# llrf_fmc_ext_female.net
KiCad netlist of a schematic drawn in Altium Designer
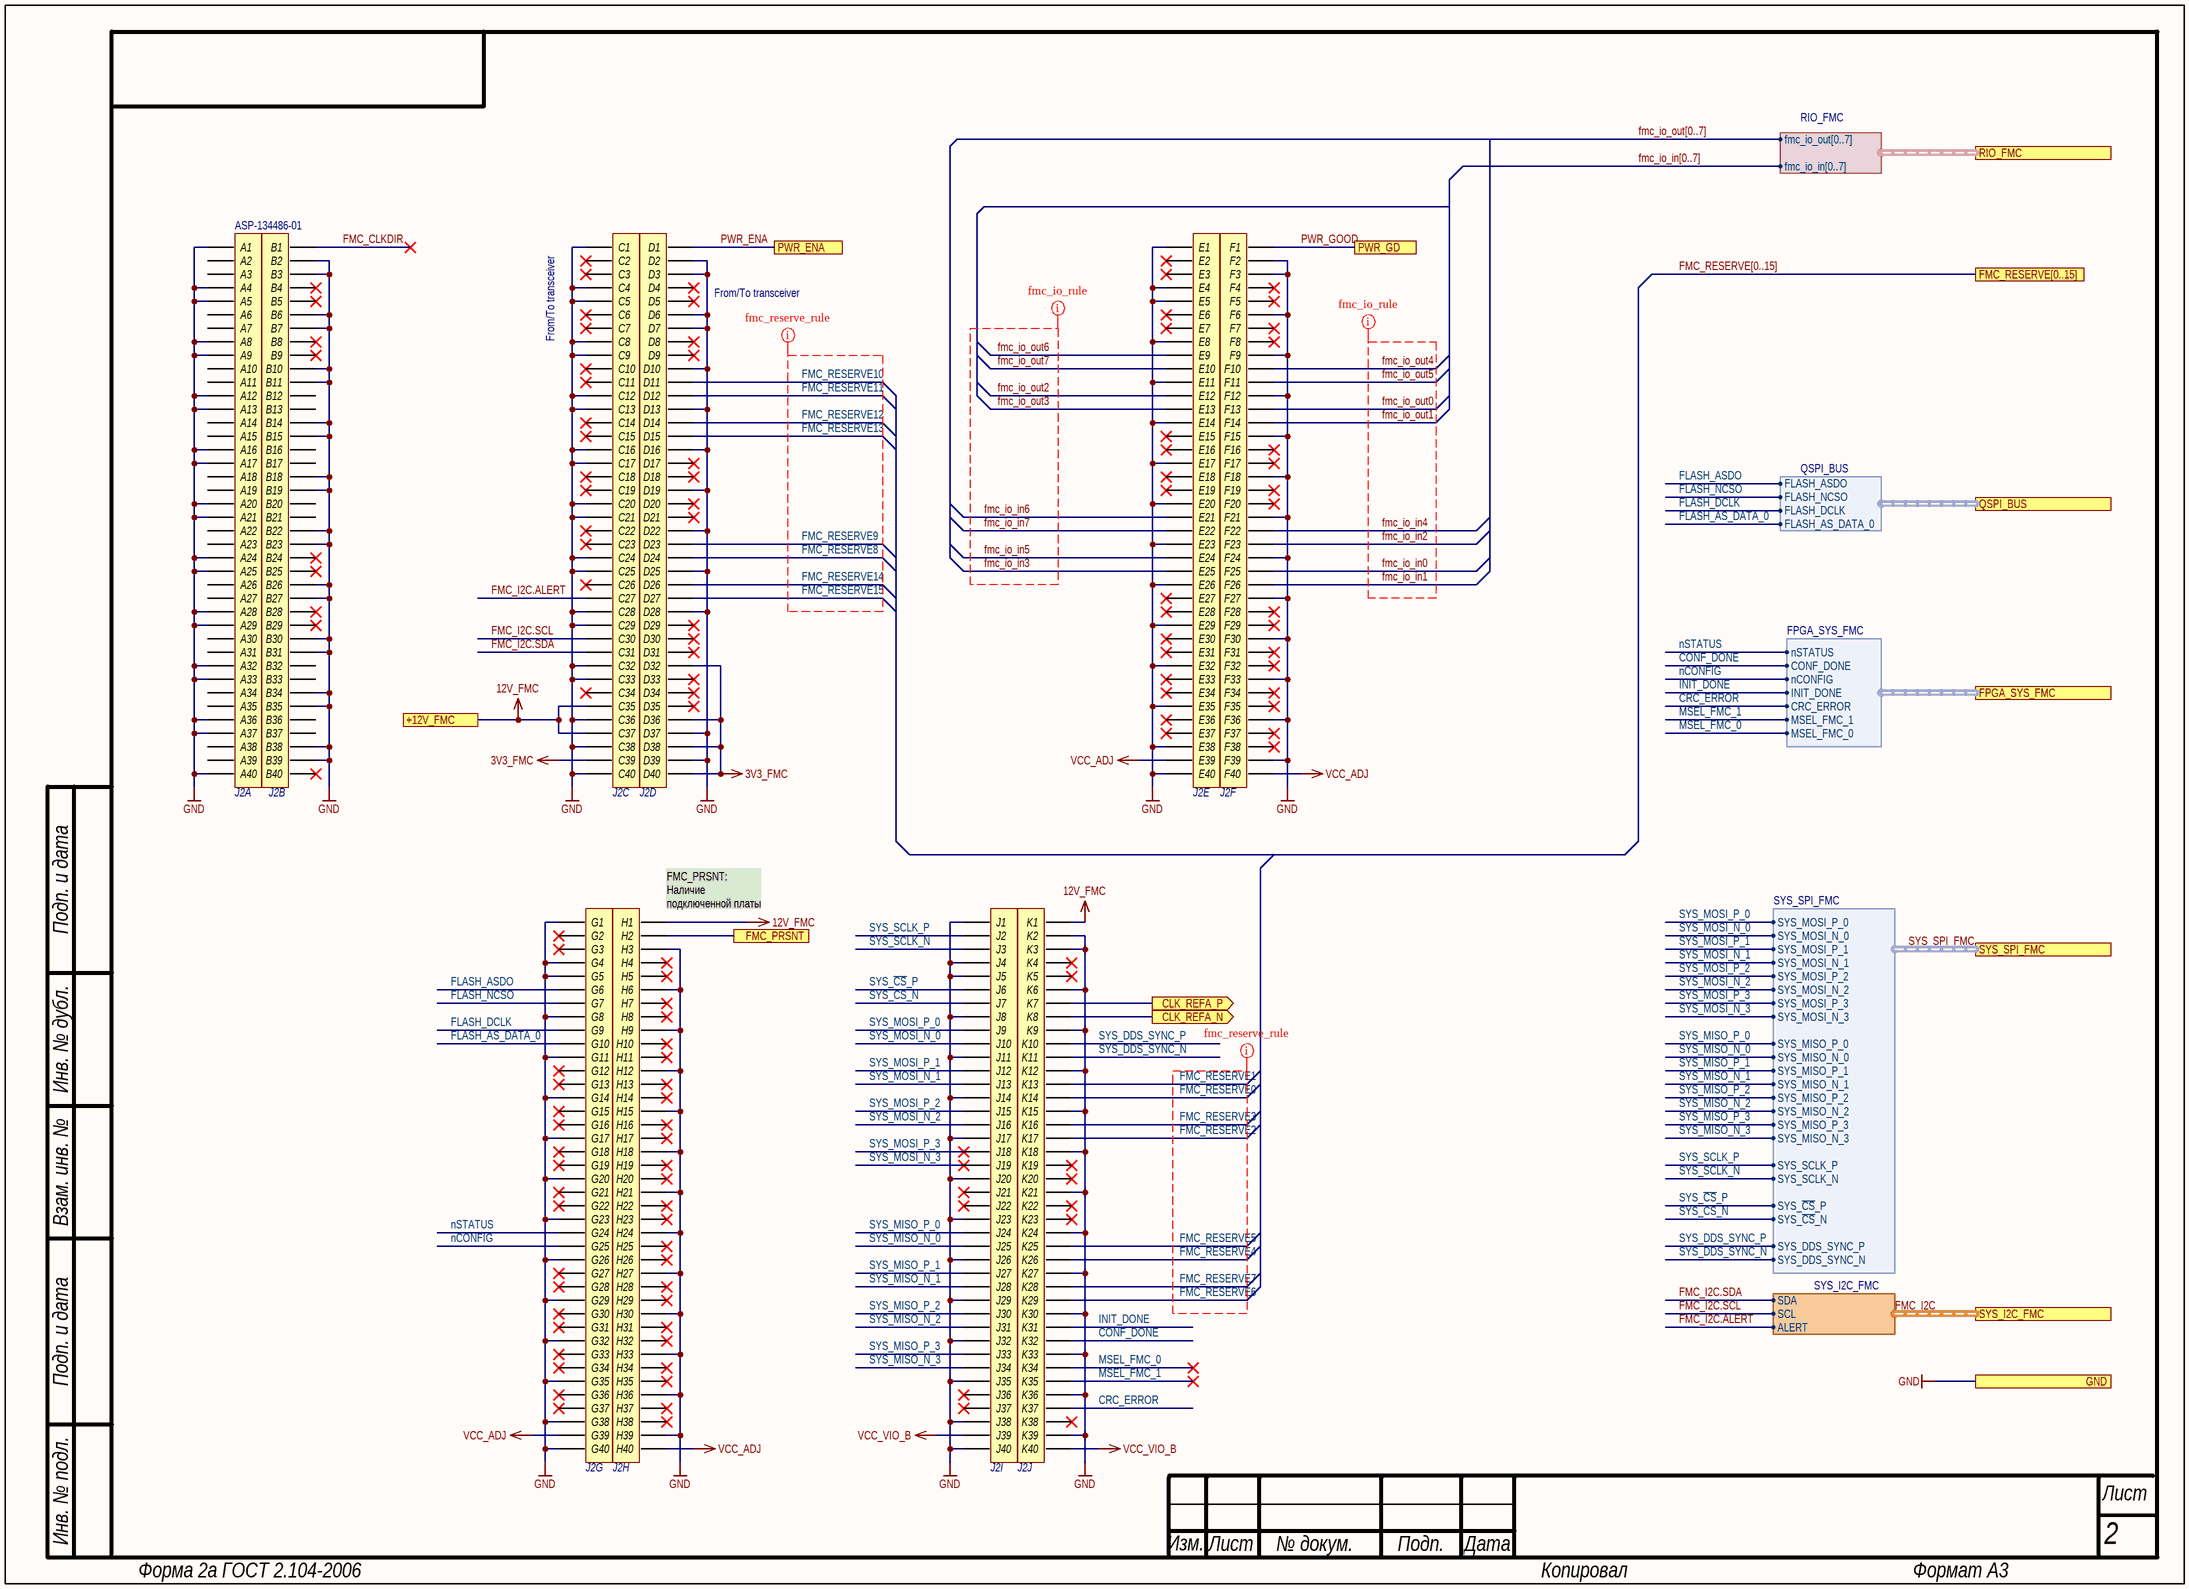
[diagram p0: llrf_fmc_ext_female.SchDoc]

(export (version "E")
  (design (tool "Eeschema 10.0.6"))
  (components
    (comp (ref "J2")
      (value "ASP-134486-01")
      (footprint "ASP-134486-01")
      (description "FMC, HPC, Terminal Array Assembly, Surface Mount, 0.050\" Pitch, 400 Pins")
      (fields
        (field (name "MANUFACTURER") "SAMTEC")
        (field (name "НАИМЕНОВАНИЕ") "ASP-134486-01")
        (field (name "CREATED") "March 24, 2015 - Wendy Xin")
      )
      (libsource (lib "Connector") (part "ASP-134486-01"))
    )
  )
  (nets
    (net (code "6") (name "/CLK_REFA_N") (class "Default")
      (node (ref "J2") (pin "K8") (pinfunction "K8_K8") (pintype "passive"))
    )
    (net (code "7") (name "/CLK_REFA_P") (class "Default")
      (node (ref "J2") (pin "K7") (pinfunction "K7_K7") (pintype "passive"))
    )
    (net (code "8") (name "/CONF_DONE") (class "Default")
      (node (ref "J2") (pin "K32") (pinfunction "K32_K32") (pintype "passive"))
    )
    (net (code "9") (name "/CRC_ERROR") (class "Default")
      (node (ref "J2") (pin "K37") (pinfunction "K37_K37") (pintype "passive"))
    )
    (net (code "10") (name "/FLASH_ASDO") (class "Default")
      (node (ref "J2") (pin "G6") (pinfunction "G6_G6") (pintype "passive"))
    )
    (net (code "11") (name "/FLASH_AS_DATA_0") (class "Default")
      (node (ref "J2") (pin "G10") (pinfunction "G10_G10") (pintype "passive"))
    )
    (net (code "12") (name "/FLASH_DCLK") (class "Default")
      (node (ref "J2") (pin "G9") (pinfunction "G9_G9") (pintype "passive"))
    )
    (net (code "13") (name "/FLASH_NCSO") (class "Default")
      (node (ref "J2") (pin "G7") (pinfunction "G7_G7") (pintype "passive"))
    )
    (net (code "14") (name "/FMC_CLKDIR") (class "Default")
      (node (ref "J2") (pin "B1") (pinfunction "B1_B1") (pintype "passive+no_connect"))
    )
    (net (code "15") (name "/FMC_I2C.ALERT") (class "Default")
      (node (ref "J2") (pin "C27") (pinfunction "C27_C27") (pintype "passive"))
    )
    (net (code "16") (name "/FMC_I2C.SCL") (class "Default")
      (node (ref "J2") (pin "C30") (pinfunction "C30_C30") (pintype "passive"))
    )
    (net (code "17") (name "/FMC_I2C.SDA") (class "Default")
      (node (ref "J2") (pin "C31") (pinfunction "C31_C31") (pintype "passive"))
    )
    (net (code "19") (name "/FMC_PRSNT") (class "Default")
      (node (ref "J2") (pin "H2") (pinfunction "H2_H2") (pintype "passive"))
    )
    (net (code "20") (name "/FMC_RESERVE0") (class "Default")
      (node (ref "J2") (pin "K14") (pinfunction "K14_K14") (pintype "passive"))
    )
    (net (code "21") (name "/FMC_RESERVE1") (class "Default")
      (node (ref "J2") (pin "K13") (pinfunction "K13_K13") (pintype "passive"))
    )
    (net (code "22") (name "/FMC_RESERVE2") (class "Default")
      (node (ref "J2") (pin "K17") (pinfunction "K17_K17") (pintype "passive"))
    )
    (net (code "23") (name "/FMC_RESERVE3") (class "Default")
      (node (ref "J2") (pin "K16") (pinfunction "K16_K16") (pintype "passive"))
    )
    (net (code "24") (name "/FMC_RESERVE4") (class "Default")
      (node (ref "J2") (pin "K26") (pinfunction "K26_K26") (pintype "passive"))
    )
    (net (code "25") (name "/FMC_RESERVE5") (class "Default")
      (node (ref "J2") (pin "K25") (pinfunction "K25_K25") (pintype "passive"))
    )
    (net (code "26") (name "/FMC_RESERVE6") (class "Default")
      (node (ref "J2") (pin "K29") (pinfunction "K29_K29") (pintype "passive"))
    )
    (net (code "27") (name "/FMC_RESERVE7") (class "Default")
      (node (ref "J2") (pin "K28") (pinfunction "K28_K28") (pintype "passive"))
    )
    (net (code "28") (name "/FMC_RESERVE8") (class "Default")
      (node (ref "J2") (pin "D24") (pinfunction "D24_D24") (pintype "passive"))
    )
    (net (code "29") (name "/FMC_RESERVE9") (class "Default")
      (node (ref "J2") (pin "D23") (pinfunction "D23_D23") (pintype "passive"))
    )
    (net (code "30") (name "/FMC_RESERVE10") (class "Default")
      (node (ref "J2") (pin "D11") (pinfunction "D11_D11") (pintype "passive"))
    )
    (net (code "31") (name "/FMC_RESERVE11") (class "Default")
      (node (ref "J2") (pin "D12") (pinfunction "D12_D12") (pintype "passive"))
    )
    (net (code "32") (name "/FMC_RESERVE12") (class "Default")
      (node (ref "J2") (pin "D14") (pinfunction "D14_D14") (pintype "passive"))
    )
    (net (code "33") (name "/FMC_RESERVE13") (class "Default")
      (node (ref "J2") (pin "D15") (pinfunction "D15_D15") (pintype "passive"))
    )
    (net (code "34") (name "/FMC_RESERVE14") (class "Default")
      (node (ref "J2") (pin "D26") (pinfunction "D26_D26") (pintype "passive"))
    )
    (net (code "35") (name "/FMC_RESERVE15") (class "Default")
      (node (ref "J2") (pin "D27") (pinfunction "D27_D27") (pintype "passive"))
    )
    (net (code "37") (name "/INIT_DONE") (class "Default")
      (node (ref "J2") (pin "K31") (pinfunction "K31_K31") (pintype "passive"))
    )
    (net (code "38") (name "/MSEL_FMC_0") (class "Default")
      (node (ref "J2") (pin "K34") (pinfunction "K34_K34") (pintype "passive+no_connect"))
    )
    (net (code "39") (name "/MSEL_FMC_1") (class "Default")
      (node (ref "J2") (pin "K35") (pinfunction "K35_K35") (pintype "passive+no_connect"))
    )
    (net (code "40") (name "/PWR_ENA") (class "Default")
      (node (ref "J2") (pin "D1") (pinfunction "D1_D1") (pintype "passive"))
    )
    (net (code "41") (name "/PWR_GOOD") (class "Default")
      (node (ref "J2") (pin "F1") (pinfunction "F1_F1") (pintype "passive"))
    )
    (net (code "43") (name "/SYS_DDS_SYNC_N") (class "Default")
      (node (ref "J2") (pin "K11") (pinfunction "K11_K11") (pintype "passive"))
    )
    (net (code "44") (name "/SYS_DDS_SYNC_P") (class "Default")
      (node (ref "J2") (pin "K10") (pinfunction "K10_K10") (pintype "passive"))
    )
    (net (code "45") (name "/SYS_MISO_N_0") (class "Default")
      (node (ref "J2") (pin "J25") (pinfunction "J25_J25") (pintype "passive"))
    )
    (net (code "46") (name "/SYS_MISO_N_1") (class "Default")
      (node (ref "J2") (pin "J28") (pinfunction "J28_J28") (pintype "passive"))
    )
    (net (code "47") (name "/SYS_MISO_N_2") (class "Default")
      (node (ref "J2") (pin "J31") (pinfunction "J31_J31") (pintype "passive"))
    )
    (net (code "48") (name "/SYS_MISO_N_3") (class "Default")
      (node (ref "J2") (pin "J34") (pinfunction "J34_J34") (pintype "passive"))
    )
    (net (code "49") (name "/SYS_MISO_P_0") (class "Default")
      (node (ref "J2") (pin "J24") (pinfunction "J24_J24") (pintype "passive"))
    )
    (net (code "50") (name "/SYS_MISO_P_1") (class "Default")
      (node (ref "J2") (pin "J27") (pinfunction "J27_J27") (pintype "passive"))
    )
    (net (code "51") (name "/SYS_MISO_P_2") (class "Default")
      (node (ref "J2") (pin "J30") (pinfunction "J30_J30") (pintype "passive"))
    )
    (net (code "52") (name "/SYS_MISO_P_3") (class "Default")
      (node (ref "J2") (pin "J33") (pinfunction "J33_J33") (pintype "passive"))
    )
    (net (code "53") (name "/SYS_MOSI_N_0") (class "Default")
      (node (ref "J2") (pin "J10") (pinfunction "J10_J10") (pintype "passive"))
    )
    (net (code "54") (name "/SYS_MOSI_N_1") (class "Default")
      (node (ref "J2") (pin "J13") (pinfunction "J13_J13") (pintype "passive"))
    )
    (net (code "55") (name "/SYS_MOSI_N_2") (class "Default")
      (node (ref "J2") (pin "J16") (pinfunction "J16_J16") (pintype "passive"))
    )
    (net (code "56") (name "/SYS_MOSI_N_3") (class "Default")
      (node (ref "J2") (pin "J19") (pinfunction "J19_J19") (pintype "passive"))
    )
    (net (code "57") (name "/SYS_MOSI_P_0") (class "Default")
      (node (ref "J2") (pin "J9") (pinfunction "J9_J9") (pintype "passive"))
    )
    (net (code "58") (name "/SYS_MOSI_P_1") (class "Default")
      (node (ref "J2") (pin "J12") (pinfunction "J12_J12") (pintype "passive"))
    )
    (net (code "59") (name "/SYS_MOSI_P_2") (class "Default")
      (node (ref "J2") (pin "J15") (pinfunction "J15_J15") (pintype "passive"))
    )
    (net (code "60") (name "/SYS_MOSI_P_3") (class "Default")
      (node (ref "J2") (pin "J18") (pinfunction "J18_J18") (pintype "passive"))
    )
    (net (code "61") (name "/SYS_SCLK_N") (class "Default")
      (node (ref "J2") (pin "J3") (pinfunction "J3_J3") (pintype "passive"))
    )
    (net (code "62") (name "/SYS_SCLK_P") (class "Default")
      (node (ref "J2") (pin "J2") (pinfunction "J2_J2") (pintype "passive"))
    )
    (net (code "64") (name "/SYS_~{CS}_N") (class "Default")
      (node (ref "J2") (pin "J7") (pinfunction "J7_J7") (pintype "passive"))
    )
    (net (code "65") (name "/SYS_~{CS}_P") (class "Default")
      (node (ref "J2") (pin "J6") (pinfunction "J6_J6") (pintype "passive"))
    )
    (net (code "66") (name "/fmc_io_in0") (class "Default")
      (node (ref "J2") (pin "F25") (pinfunction "F25_F25") (pintype "passive"))
    )
    (net (code "67") (name "/fmc_io_in1") (class "Default")
      (node (ref "J2") (pin "F26") (pinfunction "F26_F26") (pintype "passive"))
    )
    (net (code "68") (name "/fmc_io_in2") (class "Default")
      (node (ref "J2") (pin "F23") (pinfunction "F23_F23") (pintype "passive"))
    )
    (net (code "69") (name "/fmc_io_in3") (class "Default")
      (node (ref "J2") (pin "E25") (pinfunction "E25_E25") (pintype "passive"))
    )
    (net (code "70") (name "/fmc_io_in4") (class "Default")
      (node (ref "J2") (pin "F22") (pinfunction "F22_F22") (pintype "passive"))
    )
    (net (code "71") (name "/fmc_io_in5") (class "Default")
      (node (ref "J2") (pin "E24") (pinfunction "E24_E24") (pintype "passive"))
    )
    (net (code "72") (name "/fmc_io_in6") (class "Default")
      (node (ref "J2") (pin "E21") (pinfunction "E21_E21") (pintype "passive"))
    )
    (net (code "73") (name "/fmc_io_in7") (class "Default")
      (node (ref "J2") (pin "E22") (pinfunction "E22_E22") (pintype "passive"))
    )
    (net (code "75") (name "/fmc_io_out0") (class "Default")
      (node (ref "J2") (pin "F13") (pinfunction "F13_F13") (pintype "passive"))
    )
    (net (code "76") (name "/fmc_io_out1") (class "Default")
      (node (ref "J2") (pin "F14") (pinfunction "F14_F14") (pintype "passive"))
    )
    (net (code "77") (name "/fmc_io_out2") (class "Default")
      (node (ref "J2") (pin "E12") (pinfunction "E12_E12") (pintype "passive"))
    )
    (net (code "78") (name "/fmc_io_out3") (class "Default")
      (node (ref "J2") (pin "E13") (pinfunction "E13_E13") (pintype "passive"))
    )
    (net (code "79") (name "/fmc_io_out4") (class "Default")
      (node (ref "J2") (pin "F10") (pinfunction "F10_F10") (pintype "passive"))
    )
    (net (code "80") (name "/fmc_io_out5") (class "Default")
      (node (ref "J2") (pin "F11") (pinfunction "F11_F11") (pintype "passive"))
    )
    (net (code "81") (name "/fmc_io_out6") (class "Default")
      (node (ref "J2") (pin "E9") (pinfunction "E9_E9") (pintype "passive"))
    )
    (net (code "82") (name "/fmc_io_out7") (class "Default")
      (node (ref "J2") (pin "E10") (pinfunction "E10_E10") (pintype "passive"))
    )
    (net (code "83") (name "/nCONFIG") (class "Default")
      (node (ref "J2") (pin "G25") (pinfunction "G25_G25") (pintype "passive"))
    )
    (net (code "84") (name "/nSTATUS") (class "Default")
      (node (ref "J2") (pin "G24") (pinfunction "G24_G24") (pintype "passive"))
    )
    (net (code "88") (name "3V3_FMC") (class "Default")
      (node (ref "J2") (pin "C39") (pinfunction "C39_C39") (pintype "passive"))
      (node (ref "J2") (pin "D32") (pinfunction "D32_D32") (pintype "passive"))
      (node (ref "J2") (pin "D36") (pinfunction "D36_D36") (pintype "passive"))
      (node (ref "J2") (pin "D38") (pinfunction "D38_D38") (pintype "passive"))
      (node (ref "J2") (pin "D40") (pinfunction "D40_D40") (pintype "passive"))
    )
    (net (code "89") (name "12V_FMC") (class "Default")
      (node (ref "J2") (pin "C35") (pinfunction "C35_C35") (pintype "passive"))
      (node (ref "J2") (pin "C37") (pinfunction "C37_C37") (pintype "passive"))
      (node (ref "J2") (pin "H1") (pinfunction "H1_H1") (pintype "passive"))
      (node (ref "J2") (pin "K1") (pinfunction "K1_K1") (pintype "passive"))
    )
    (net (code "90") (name "GND") (class "Default")
      (node (ref "J2") (pin "A1") (pinfunction "A1_A1") (pintype "passive"))
      (node (ref "J2") (pin "A12") (pinfunction "A12_A12") (pintype "passive"))
      (node (ref "J2") (pin "A13") (pinfunction "A13_A13") (pintype "passive"))
      (node (ref "J2") (pin "A16") (pinfunction "A16_A16") (pintype "passive"))
      (node (ref "J2") (pin "A17") (pinfunction "A17_A17") (pintype "passive"))
      (node (ref "J2") (pin "A20") (pinfunction "A20_A20") (pintype "passive"))
      (node (ref "J2") (pin "A21") (pinfunction "A21_A21") (pintype "passive"))
      (node (ref "J2") (pin "A24") (pinfunction "A24_A24") (pintype "passive"))
      (node (ref "J2") (pin "A25") (pinfunction "A25_A25") (pintype "passive"))
      (node (ref "J2") (pin "A28") (pinfunction "A28_A28") (pintype "passive"))
      (node (ref "J2") (pin "A29") (pinfunction "A29_A29") (pintype "passive"))
      (node (ref "J2") (pin "A32") (pinfunction "A32_A32") (pintype "passive"))
      (node (ref "J2") (pin "A33") (pinfunction "A33_A33") (pintype "passive"))
      (node (ref "J2") (pin "A36") (pinfunction "A36_A36") (pintype "passive"))
      (node (ref "J2") (pin "A37") (pinfunction "A37_A37") (pintype "passive"))
      (node (ref "J2") (pin "A4") (pinfunction "A4_A4") (pintype "passive"))
      (node (ref "J2") (pin "A40") (pinfunction "A40_A40") (pintype "passive"))
      (node (ref "J2") (pin "A5") (pinfunction "A5_A5") (pintype "passive"))
      (node (ref "J2") (pin "A8") (pinfunction "A8_A8") (pintype "passive"))
      (node (ref "J2") (pin "A9") (pinfunction "A9_A9") (pintype "passive"))
      (node (ref "J2") (pin "B10") (pinfunction "B10_B10") (pintype "passive"))
      (node (ref "J2") (pin "B11") (pinfunction "B11_B11") (pintype "passive"))
      (node (ref "J2") (pin "B14") (pinfunction "B14_B14") (pintype "passive"))
      (node (ref "J2") (pin "B15") (pinfunction "B15_B15") (pintype "passive"))
      (node (ref "J2") (pin "B18") (pinfunction "B18_B18") (pintype "passive"))
      (node (ref "J2") (pin "B19") (pinfunction "B19_B19") (pintype "passive"))
      (node (ref "J2") (pin "B2") (pinfunction "B2_B2") (pintype "passive"))
      (node (ref "J2") (pin "B22") (pinfunction "B22_B22") (pintype "passive"))
      (node (ref "J2") (pin "B23") (pinfunction "B23_B23") (pintype "passive"))
      (node (ref "J2") (pin "B26") (pinfunction "B26_B26") (pintype "passive"))
      (node (ref "J2") (pin "B27") (pinfunction "B27_B27") (pintype "passive"))
      (node (ref "J2") (pin "B3") (pinfunction "B3_B3") (pintype "passive"))
      (node (ref "J2") (pin "B30") (pinfunction "B30_B30") (pintype "passive"))
      (node (ref "J2") (pin "B31") (pinfunction "B31_B31") (pintype "passive"))
      (node (ref "J2") (pin "B34") (pinfunction "B34_B34") (pintype "passive"))
      (node (ref "J2") (pin "B35") (pinfunction "B35_B35") (pintype "passive"))
      (node (ref "J2") (pin "B38") (pinfunction "B38_B38") (pintype "passive"))
      (node (ref "J2") (pin "B39") (pinfunction "B39_B39") (pintype "passive"))
      (node (ref "J2") (pin "B6") (pinfunction "B6_B6") (pintype "passive"))
      (node (ref "J2") (pin "B7") (pinfunction "B7_B7") (pintype "passive"))
      (node (ref "J2") (pin "C1") (pinfunction "C1_C1") (pintype "passive"))
      (node (ref "J2") (pin "C12") (pinfunction "C12_C12") (pintype "passive"))
      (node (ref "J2") (pin "C13") (pinfunction "C13_C13") (pintype "passive"))
      (node (ref "J2") (pin "C16") (pinfunction "C16_C16") (pintype "passive"))
      (node (ref "J2") (pin "C17") (pinfunction "C17_C17") (pintype "passive"))
      (node (ref "J2") (pin "C20") (pinfunction "C20_C20") (pintype "passive"))
      (node (ref "J2") (pin "C21") (pinfunction "C21_C21") (pintype "passive"))
      (node (ref "J2") (pin "C24") (pinfunction "C24_C24") (pintype "passive"))
      (node (ref "J2") (pin "C25") (pinfunction "C25_C25") (pintype "passive"))
      (node (ref "J2") (pin "C28") (pinfunction "C28_C28") (pintype "passive"))
      (node (ref "J2") (pin "C29") (pinfunction "C29_C29") (pintype "passive"))
      (node (ref "J2") (pin "C32") (pinfunction "C32_C32") (pintype "passive"))
      (node (ref "J2") (pin "C33") (pinfunction "C33_C33") (pintype "passive"))
      (node (ref "J2") (pin "C36") (pinfunction "C36_C36") (pintype "passive"))
      (node (ref "J2") (pin "C38") (pinfunction "C38_C38") (pintype "passive"))
      (node (ref "J2") (pin "C4") (pinfunction "C4_C4") (pintype "passive"))
      (node (ref "J2") (pin "C40") (pinfunction "C40_C40") (pintype "passive"))
      (node (ref "J2") (pin "C5") (pinfunction "C5_C5") (pintype "passive"))
      (node (ref "J2") (pin "C8") (pinfunction "C8_C8") (pintype "passive"))
      (node (ref "J2") (pin "C9") (pinfunction "C9_C9") (pintype "passive"))
      (node (ref "J2") (pin "D10") (pinfunction "D10_D10") (pintype "passive"))
      (node (ref "J2") (pin "D13") (pinfunction "D13_D13") (pintype "passive"))
      (node (ref "J2") (pin "D16") (pinfunction "D16_D16") (pintype "passive"))
      (node (ref "J2") (pin "D19") (pinfunction "D19_D19") (pintype "passive"))
      (node (ref "J2") (pin "D2") (pinfunction "D2_D2") (pintype "passive"))
      (node (ref "J2") (pin "D22") (pinfunction "D22_D22") (pintype "passive"))
      (node (ref "J2") (pin "D25") (pinfunction "D25_D25") (pintype "passive"))
      (node (ref "J2") (pin "D28") (pinfunction "D28_D28") (pintype "passive"))
      (node (ref "J2") (pin "D3") (pinfunction "D3_D3") (pintype "passive"))
      (node (ref "J2") (pin "D37") (pinfunction "D37_D37") (pintype "passive"))
      (node (ref "J2") (pin "D39") (pinfunction "D39_D39") (pintype "passive"))
      (node (ref "J2") (pin "D6") (pinfunction "D6_D6") (pintype "passive"))
      (node (ref "J2") (pin "D7") (pinfunction "D7_D7") (pintype "passive"))
      (node (ref "J2") (pin "E1") (pinfunction "E1_E1") (pintype "passive"))
      (node (ref "J2") (pin "E11") (pinfunction "E11_E11") (pintype "passive"))
      (node (ref "J2") (pin "E14") (pinfunction "E14_E14") (pintype "passive"))
      (node (ref "J2") (pin "E17") (pinfunction "E17_E17") (pintype "passive"))
      (node (ref "J2") (pin "E20") (pinfunction "E20_E20") (pintype "passive"))
      (node (ref "J2") (pin "E23") (pinfunction "E23_E23") (pintype "passive"))
      (node (ref "J2") (pin "E26") (pinfunction "E26_E26") (pintype "passive"))
      (node (ref "J2") (pin "E29") (pinfunction "E29_E29") (pintype "passive"))
      (node (ref "J2") (pin "E32") (pinfunction "E32_E32") (pintype "passive"))
      (node (ref "J2") (pin "E35") (pinfunction "E35_E35") (pintype "passive"))
      (node (ref "J2") (pin "E38") (pinfunction "E38_E38") (pintype "passive"))
      (node (ref "J2") (pin "E4") (pinfunction "E4_E4") (pintype "passive"))
      (node (ref "J2") (pin "E40") (pinfunction "E40_E40") (pintype "passive"))
      (node (ref "J2") (pin "E5") (pinfunction "E5_E5") (pintype "passive"))
      (node (ref "J2") (pin "E8") (pinfunction "E8_E8") (pintype "passive"))
      (node (ref "J2") (pin "F12") (pinfunction "F12_F12") (pintype "passive"))
      (node (ref "J2") (pin "F15") (pinfunction "F15_F15") (pintype "passive"))
      (node (ref "J2") (pin "F18") (pinfunction "F18_F18") (pintype "passive"))
      (node (ref "J2") (pin "F2") (pinfunction "F2_F2") (pintype "passive"))
      (node (ref "J2") (pin "F21") (pinfunction "F21_F21") (pintype "passive"))
      (node (ref "J2") (pin "F24") (pinfunction "F24_F24") (pintype "passive"))
      (node (ref "J2") (pin "F27") (pinfunction "F27_F27") (pintype "passive"))
      (node (ref "J2") (pin "F3") (pinfunction "F3_F3") (pintype "passive"))
      (node (ref "J2") (pin "F30") (pinfunction "F30_F30") (pintype "passive"))
      (node (ref "J2") (pin "F33") (pinfunction "F33_F33") (pintype "passive"))
      (node (ref "J2") (pin "F36") (pinfunction "F36_F36") (pintype "passive"))
      (node (ref "J2") (pin "F39") (pinfunction "F39_F39") (pintype "passive"))
      (node (ref "J2") (pin "F6") (pinfunction "F6_F6") (pintype "passive"))
      (node (ref "J2") (pin "F9") (pinfunction "F9_F9") (pintype "passive"))
      (node (ref "J2") (pin "G1") (pinfunction "G1_G1") (pintype "passive"))
      (node (ref "J2") (pin "G11") (pinfunction "G11_G11") (pintype "passive"))
      (node (ref "J2") (pin "G14") (pinfunction "G14_G14") (pintype "passive"))
      (node (ref "J2") (pin "G17") (pinfunction "G17_G17") (pintype "passive"))
      (node (ref "J2") (pin "G20") (pinfunction "G20_G20") (pintype "passive"))
      (node (ref "J2") (pin "G23") (pinfunction "G23_G23") (pintype "passive"))
      (node (ref "J2") (pin "G26") (pinfunction "G26_G26") (pintype "passive"))
      (node (ref "J2") (pin "G29") (pinfunction "G29_G29") (pintype "passive"))
      (node (ref "J2") (pin "G32") (pinfunction "G32_G32") (pintype "passive"))
      (node (ref "J2") (pin "G35") (pinfunction "G35_G35") (pintype "passive"))
      (node (ref "J2") (pin "G38") (pinfunction "G38_G38") (pintype "passive"))
      (node (ref "J2") (pin "G4") (pinfunction "G4_G4") (pintype "passive"))
      (node (ref "J2") (pin "G40") (pinfunction "G40_G40") (pintype "passive"))
      (node (ref "J2") (pin "G5") (pinfunction "G5_G5") (pintype "passive"))
      (node (ref "J2") (pin "G8") (pinfunction "G8_G8") (pintype "passive"))
      (node (ref "J2") (pin "H12") (pinfunction "H12_H12") (pintype "passive"))
      (node (ref "J2") (pin "H15") (pinfunction "H15_H15") (pintype "passive"))
      (node (ref "J2") (pin "H18") (pinfunction "H18_H18") (pintype "passive"))
      (node (ref "J2") (pin "H21") (pinfunction "H21_H21") (pintype "passive"))
      (node (ref "J2") (pin "H24") (pinfunction "H24_H24") (pintype "passive"))
      (node (ref "J2") (pin "H27") (pinfunction "H27_H27") (pintype "passive"))
      (node (ref "J2") (pin "H3") (pinfunction "H3_H3") (pintype "passive"))
      (node (ref "J2") (pin "H30") (pinfunction "H30_H30") (pintype "passive"))
      (node (ref "J2") (pin "H33") (pinfunction "H33_H33") (pintype "passive"))
      (node (ref "J2") (pin "H36") (pinfunction "H36_H36") (pintype "passive"))
      (node (ref "J2") (pin "H39") (pinfunction "H39_H39") (pintype "passive"))
      (node (ref "J2") (pin "H6") (pinfunction "H6_H6") (pintype "passive"))
      (node (ref "J2") (pin "H9") (pinfunction "H9_H9") (pintype "passive"))
      (node (ref "J2") (pin "J1") (pinfunction "J1_J1") (pintype "passive"))
      (node (ref "J2") (pin "J11") (pinfunction "J11_J11") (pintype "passive"))
      (node (ref "J2") (pin "J14") (pinfunction "J14_J14") (pintype "passive"))
      (node (ref "J2") (pin "J17") (pinfunction "J17_J17") (pintype "passive"))
      (node (ref "J2") (pin "J20") (pinfunction "J20_J20") (pintype "passive"))
      (node (ref "J2") (pin "J23") (pinfunction "J23_J23") (pintype "passive"))
      (node (ref "J2") (pin "J26") (pinfunction "J26_J26") (pintype "passive"))
      (node (ref "J2") (pin "J29") (pinfunction "J29_J29") (pintype "passive"))
      (node (ref "J2") (pin "J32") (pinfunction "J32_J32") (pintype "passive"))
      (node (ref "J2") (pin "J35") (pinfunction "J35_J35") (pintype "passive"))
      (node (ref "J2") (pin "J38") (pinfunction "J38_J38") (pintype "passive"))
      (node (ref "J2") (pin "J4") (pinfunction "J4_J4") (pintype "passive"))
      (node (ref "J2") (pin "J40") (pinfunction "J40_J40") (pintype "passive"))
      (node (ref "J2") (pin "J5") (pinfunction "J5_J5") (pintype "passive"))
      (node (ref "J2") (pin "J8") (pinfunction "J8_J8") (pintype "passive"))
      (node (ref "J2") (pin "K12") (pinfunction "K12_K12") (pintype "passive"))
      (node (ref "J2") (pin "K15") (pinfunction "K15_K15") (pintype "passive"))
      (node (ref "J2") (pin "K18") (pinfunction "K18_K18") (pintype "passive"))
      (node (ref "J2") (pin "K2") (pinfunction "K2_K2") (pintype "passive"))
      (node (ref "J2") (pin "K21") (pinfunction "K21_K21") (pintype "passive"))
      (node (ref "J2") (pin "K24") (pinfunction "K24_K24") (pintype "passive"))
      (node (ref "J2") (pin "K27") (pinfunction "K27_K27") (pintype "passive"))
      (node (ref "J2") (pin "K3") (pinfunction "K3_K3") (pintype "passive"))
      (node (ref "J2") (pin "K30") (pinfunction "K30_K30") (pintype "passive"))
      (node (ref "J2") (pin "K33") (pinfunction "K33_K33") (pintype "passive"))
      (node (ref "J2") (pin "K36") (pinfunction "K36_K36") (pintype "passive"))
      (node (ref "J2") (pin "K39") (pinfunction "K39_K39") (pintype "passive"))
      (node (ref "J2") (pin "K6") (pinfunction "K6_K6") (pintype "passive"))
      (node (ref "J2") (pin "K9") (pinfunction "K9_K9") (pintype "passive"))
    )
    (net (code "91") (name "VCC_ADJ") (class "Default")
      (node (ref "J2") (pin "E39") (pinfunction "E39_E39") (pintype "passive"))
      (node (ref "J2") (pin "F40") (pinfunction "F40_F40") (pintype "passive"))
      (node (ref "J2") (pin "G39") (pinfunction "G39_G39") (pintype "passive"))
      (node (ref "J2") (pin "H40") (pinfunction "H40_H40") (pintype "passive"))
    )
    (net (code "92") (name "VCC_VIO_B") (class "Default")
      (node (ref "J2") (pin "J39") (pinfunction "J39_J39") (pintype "passive"))
      (node (ref "J2") (pin "K40") (pinfunction "K40_K40") (pintype "passive"))
    )
    (net (code "93") (name "unconnected-(J2-PadA2)") (class "Default")
      (node (ref "J2") (pin "A2") (pinfunction "A2_A2") (pintype "passive"))
    )
    (net (code "94") (name "unconnected-(J2-PadA3)") (class "Default")
      (node (ref "J2") (pin "A3") (pinfunction "A3_A3") (pintype "passive"))
    )
    (net (code "95") (name "unconnected-(J2-PadA6)") (class "Default")
      (node (ref "J2") (pin "A6") (pinfunction "A6_A6") (pintype "passive"))
    )
    (net (code "96") (name "unconnected-(J2-PadA7)") (class "Default")
      (node (ref "J2") (pin "A7") (pinfunction "A7_A7") (pintype "passive"))
    )
    (net (code "97") (name "unconnected-(J2-PadA10)") (class "Default")
      (node (ref "J2") (pin "A10") (pinfunction "A10_A10") (pintype "passive"))
    )
    (net (code "98") (name "unconnected-(J2-PadA11)") (class "Default")
      (node (ref "J2") (pin "A11") (pinfunction "A11_A11") (pintype "passive"))
    )
    (net (code "99") (name "unconnected-(J2-PadA14)") (class "Default")
      (node (ref "J2") (pin "A14") (pinfunction "A14_A14") (pintype "passive"))
    )
    (net (code "100") (name "unconnected-(J2-PadA15)") (class "Default")
      (node (ref "J2") (pin "A15") (pinfunction "A15_A15") (pintype "passive"))
    )
    (net (code "101") (name "unconnected-(J2-PadA18)") (class "Default")
      (node (ref "J2") (pin "A18") (pinfunction "A18_A18") (pintype "passive"))
    )
    (net (code "102") (name "unconnected-(J2-PadA19)") (class "Default")
      (node (ref "J2") (pin "A19") (pinfunction "A19_A19") (pintype "passive"))
    )
    (net (code "103") (name "unconnected-(J2-PadA22)") (class "Default")
      (node (ref "J2") (pin "A22") (pinfunction "A22_A22") (pintype "passive"))
    )
    (net (code "104") (name "unconnected-(J2-PadA23)") (class "Default")
      (node (ref "J2") (pin "A23") (pinfunction "A23_A23") (pintype "passive"))
    )
    (net (code "105") (name "unconnected-(J2-PadA26)") (class "Default")
      (node (ref "J2") (pin "A26") (pinfunction "A26_A26") (pintype "passive"))
    )
    (net (code "106") (name "unconnected-(J2-PadA27)") (class "Default")
      (node (ref "J2") (pin "A27") (pinfunction "A27_A27") (pintype "passive"))
    )
    (net (code "107") (name "unconnected-(J2-PadA30)") (class "Default")
      (node (ref "J2") (pin "A30") (pinfunction "A30_A30") (pintype "passive"))
    )
    (net (code "108") (name "unconnected-(J2-PadA31)") (class "Default")
      (node (ref "J2") (pin "A31") (pinfunction "A31_A31") (pintype "passive"))
    )
    (net (code "109") (name "unconnected-(J2-PadA34)") (class "Default")
      (node (ref "J2") (pin "A34") (pinfunction "A34_A34") (pintype "passive"))
    )
    (net (code "110") (name "unconnected-(J2-PadA35)") (class "Default")
      (node (ref "J2") (pin "A35") (pinfunction "A35_A35") (pintype "passive"))
    )
    (net (code "111") (name "unconnected-(J2-PadA38)") (class "Default")
      (node (ref "J2") (pin "A38") (pinfunction "A38_A38") (pintype "passive"))
    )
    (net (code "112") (name "unconnected-(J2-PadA39)") (class "Default")
      (node (ref "J2") (pin "A39") (pinfunction "A39_A39") (pintype "passive"))
    )
    (net (code "113") (name "unconnected-(J2-PadB4)") (class "Default")
      (node (ref "J2") (pin "B4") (pinfunction "B4_B4") (pintype "passive+no_connect"))
    )
    (net (code "114") (name "unconnected-(J2-PadB5)") (class "Default")
      (node (ref "J2") (pin "B5") (pinfunction "B5_B5") (pintype "passive+no_connect"))
    )
    (net (code "115") (name "unconnected-(J2-PadB8)") (class "Default")
      (node (ref "J2") (pin "B8") (pinfunction "B8_B8") (pintype "passive+no_connect"))
    )
    (net (code "116") (name "unconnected-(J2-PadB9)") (class "Default")
      (node (ref "J2") (pin "B9") (pinfunction "B9_B9") (pintype "passive+no_connect"))
    )
    (net (code "117") (name "unconnected-(J2-PadB12)") (class "Default")
      (node (ref "J2") (pin "B12") (pinfunction "B12_B12") (pintype "passive"))
    )
    (net (code "118") (name "unconnected-(J2-PadB13)") (class "Default")
      (node (ref "J2") (pin "B13") (pinfunction "B13_B13") (pintype "passive"))
    )
    (net (code "119") (name "unconnected-(J2-PadB16)") (class "Default")
      (node (ref "J2") (pin "B16") (pinfunction "B16_B16") (pintype "passive"))
    )
    (net (code "120") (name "unconnected-(J2-PadB17)") (class "Default")
      (node (ref "J2") (pin "B17") (pinfunction "B17_B17") (pintype "passive"))
    )
    (net (code "121") (name "unconnected-(J2-PadB20)") (class "Default")
      (node (ref "J2") (pin "B20") (pinfunction "B20_B20") (pintype "passive"))
    )
    (net (code "122") (name "unconnected-(J2-PadB21)") (class "Default")
      (node (ref "J2") (pin "B21") (pinfunction "B21_B21") (pintype "passive"))
    )
    (net (code "123") (name "unconnected-(J2-PadB24)") (class "Default")
      (node (ref "J2") (pin "B24") (pinfunction "B24_B24") (pintype "passive+no_connect"))
    )
    (net (code "124") (name "unconnected-(J2-PadB25)") (class "Default")
      (node (ref "J2") (pin "B25") (pinfunction "B25_B25") (pintype "passive+no_connect"))
    )
    (net (code "125") (name "unconnected-(J2-PadB28)") (class "Default")
      (node (ref "J2") (pin "B28") (pinfunction "B28_B28") (pintype "passive+no_connect"))
    )
    (net (code "126") (name "unconnected-(J2-PadB29)") (class "Default")
      (node (ref "J2") (pin "B29") (pinfunction "B29_B29") (pintype "passive+no_connect"))
    )
    (net (code "127") (name "unconnected-(J2-PadB32)") (class "Default")
      (node (ref "J2") (pin "B32") (pinfunction "B32_B32") (pintype "passive"))
    )
    (net (code "128") (name "unconnected-(J2-PadB33)") (class "Default")
      (node (ref "J2") (pin "B33") (pinfunction "B33_B33") (pintype "passive"))
    )
    (net (code "129") (name "unconnected-(J2-PadB36)") (class "Default")
      (node (ref "J2") (pin "B36") (pinfunction "B36_B36") (pintype "passive"))
    )
    (net (code "130") (name "unconnected-(J2-PadB37)") (class "Default")
      (node (ref "J2") (pin "B37") (pinfunction "B37_B37") (pintype "passive"))
    )
    (net (code "131") (name "unconnected-(J2-PadB40)") (class "Default")
      (node (ref "J2") (pin "B40") (pinfunction "B40_B40") (pintype "passive+no_connect"))
    )
    (net (code "132") (name "unconnected-(J2-PadC2)") (class "Default")
      (node (ref "J2") (pin "C2") (pinfunction "C2_C2") (pintype "passive+no_connect"))
    )
    (net (code "133") (name "unconnected-(J2-PadC3)") (class "Default")
      (node (ref "J2") (pin "C3") (pinfunction "C3_C3") (pintype "passive+no_connect"))
    )
    (net (code "134") (name "unconnected-(J2-PadC6)") (class "Default")
      (node (ref "J2") (pin "C6") (pinfunction "C6_C6") (pintype "passive+no_connect"))
    )
    (net (code "135") (name "unconnected-(J2-PadC7)") (class "Default")
      (node (ref "J2") (pin "C7") (pinfunction "C7_C7") (pintype "passive+no_connect"))
    )
    (net (code "136") (name "unconnected-(J2-PadC10)") (class "Default")
      (node (ref "J2") (pin "C10") (pinfunction "C10_C10") (pintype "passive+no_connect"))
    )
    (net (code "137") (name "unconnected-(J2-PadC11)") (class "Default")
      (node (ref "J2") (pin "C11") (pinfunction "C11_C11") (pintype "passive+no_connect"))
    )
    (net (code "138") (name "unconnected-(J2-PadC14)") (class "Default")
      (node (ref "J2") (pin "C14") (pinfunction "C14_C14") (pintype "passive+no_connect"))
    )
    (net (code "139") (name "unconnected-(J2-PadC15)") (class "Default")
      (node (ref "J2") (pin "C15") (pinfunction "C15_C15") (pintype "passive+no_connect"))
    )
    (net (code "140") (name "unconnected-(J2-PadC18)") (class "Default")
      (node (ref "J2") (pin "C18") (pinfunction "C18_C18") (pintype "passive+no_connect"))
    )
    (net (code "141") (name "unconnected-(J2-PadC19)") (class "Default")
      (node (ref "J2") (pin "C19") (pinfunction "C19_C19") (pintype "passive+no_connect"))
    )
    (net (code "142") (name "unconnected-(J2-PadC22)") (class "Default")
      (node (ref "J2") (pin "C22") (pinfunction "C22_C22") (pintype "passive+no_connect"))
    )
    (net (code "143") (name "unconnected-(J2-PadC23)") (class "Default")
      (node (ref "J2") (pin "C23") (pinfunction "C23_C23") (pintype "passive+no_connect"))
    )
    (net (code "144") (name "unconnected-(J2-PadC26)") (class "Default")
      (node (ref "J2") (pin "C26") (pinfunction "C26_C26") (pintype "passive+no_connect"))
    )
    (net (code "145") (name "unconnected-(J2-PadC34)") (class "Default")
      (node (ref "J2") (pin "C34") (pinfunction "C34_C34") (pintype "passive+no_connect"))
    )
    (net (code "146") (name "unconnected-(J2-PadD4)") (class "Default")
      (node (ref "J2") (pin "D4") (pinfunction "D4_D4") (pintype "passive+no_connect"))
    )
    (net (code "147") (name "unconnected-(J2-PadD5)") (class "Default")
      (node (ref "J2") (pin "D5") (pinfunction "D5_D5") (pintype "passive+no_connect"))
    )
    (net (code "148") (name "unconnected-(J2-PadD8)") (class "Default")
      (node (ref "J2") (pin "D8") (pinfunction "D8_D8") (pintype "passive+no_connect"))
    )
    (net (code "149") (name "unconnected-(J2-PadD9)") (class "Default")
      (node (ref "J2") (pin "D9") (pinfunction "D9_D9") (pintype "passive+no_connect"))
    )
    (net (code "150") (name "unconnected-(J2-PadD17)") (class "Default")
      (node (ref "J2") (pin "D17") (pinfunction "D17_D17") (pintype "passive+no_connect"))
    )
    (net (code "151") (name "unconnected-(J2-PadD18)") (class "Default")
      (node (ref "J2") (pin "D18") (pinfunction "D18_D18") (pintype "passive+no_connect"))
    )
    (net (code "152") (name "unconnected-(J2-PadD20)") (class "Default")
      (node (ref "J2") (pin "D20") (pinfunction "D20_D20") (pintype "passive+no_connect"))
    )
    (net (code "153") (name "unconnected-(J2-PadD21)") (class "Default")
      (node (ref "J2") (pin "D21") (pinfunction "D21_D21") (pintype "passive+no_connect"))
    )
    (net (code "154") (name "unconnected-(J2-PadD29)") (class "Default")
      (node (ref "J2") (pin "D29") (pinfunction "D29_D29") (pintype "passive+no_connect"))
    )
    (net (code "155") (name "unconnected-(J2-PadD30)") (class "Default")
      (node (ref "J2") (pin "D30") (pinfunction "D30_D30") (pintype "passive+no_connect"))
    )
    (net (code "156") (name "unconnected-(J2-PadD31)") (class "Default")
      (node (ref "J2") (pin "D31") (pinfunction "D31_D31") (pintype "passive+no_connect"))
    )
    (net (code "157") (name "unconnected-(J2-PadD33)") (class "Default")
      (node (ref "J2") (pin "D33") (pinfunction "D33_D33") (pintype "passive+no_connect"))
    )
    (net (code "158") (name "unconnected-(J2-PadD34)") (class "Default")
      (node (ref "J2") (pin "D34") (pinfunction "D34_D34") (pintype "passive+no_connect"))
    )
    (net (code "159") (name "unconnected-(J2-PadD35)") (class "Default")
      (node (ref "J2") (pin "D35") (pinfunction "D35_D35") (pintype "passive+no_connect"))
    )
    (net (code "160") (name "unconnected-(J2-PadE2)") (class "Default")
      (node (ref "J2") (pin "E2") (pinfunction "E2_E2") (pintype "passive+no_connect"))
    )
    (net (code "161") (name "unconnected-(J2-PadE3)") (class "Default")
      (node (ref "J2") (pin "E3") (pinfunction "E3_E3") (pintype "passive+no_connect"))
    )
    (net (code "162") (name "unconnected-(J2-PadE6)") (class "Default")
      (node (ref "J2") (pin "E6") (pinfunction "E6_E6") (pintype "passive+no_connect"))
    )
    (net (code "163") (name "unconnected-(J2-PadE7)") (class "Default")
      (node (ref "J2") (pin "E7") (pinfunction "E7_E7") (pintype "passive+no_connect"))
    )
    (net (code "164") (name "unconnected-(J2-PadE15)") (class "Default")
      (node (ref "J2") (pin "E15") (pinfunction "E15_E15") (pintype "passive+no_connect"))
    )
    (net (code "165") (name "unconnected-(J2-PadE16)") (class "Default")
      (node (ref "J2") (pin "E16") (pinfunction "E16_E16") (pintype "passive+no_connect"))
    )
    (net (code "166") (name "unconnected-(J2-PadE18)") (class "Default")
      (node (ref "J2") (pin "E18") (pinfunction "E18_E18") (pintype "passive+no_connect"))
    )
    (net (code "167") (name "unconnected-(J2-PadE19)") (class "Default")
      (node (ref "J2") (pin "E19") (pinfunction "E19_E19") (pintype "passive+no_connect"))
    )
    (net (code "168") (name "unconnected-(J2-PadE27)") (class "Default")
      (node (ref "J2") (pin "E27") (pinfunction "E27_E27") (pintype "passive+no_connect"))
    )
    (net (code "169") (name "unconnected-(J2-PadE28)") (class "Default")
      (node (ref "J2") (pin "E28") (pinfunction "E28_E28") (pintype "passive+no_connect"))
    )
    (net (code "170") (name "unconnected-(J2-PadE30)") (class "Default")
      (node (ref "J2") (pin "E30") (pinfunction "E30_E30") (pintype "passive+no_connect"))
    )
    (net (code "171") (name "unconnected-(J2-PadE31)") (class "Default")
      (node (ref "J2") (pin "E31") (pinfunction "E31_E31") (pintype "passive+no_connect"))
    )
    (net (code "172") (name "unconnected-(J2-PadE33)") (class "Default")
      (node (ref "J2") (pin "E33") (pinfunction "E33_E33") (pintype "passive+no_connect"))
    )
    (net (code "173") (name "unconnected-(J2-PadE34)") (class "Default")
      (node (ref "J2") (pin "E34") (pinfunction "E34_E34") (pintype "passive+no_connect"))
    )
    (net (code "174") (name "unconnected-(J2-PadE36)") (class "Default")
      (node (ref "J2") (pin "E36") (pinfunction "E36_E36") (pintype "passive+no_connect"))
    )
    (net (code "175") (name "unconnected-(J2-PadE37)") (class "Default")
      (node (ref "J2") (pin "E37") (pinfunction "E37_E37") (pintype "passive+no_connect"))
    )
    (net (code "176") (name "unconnected-(J2-PadF4)") (class "Default")
      (node (ref "J2") (pin "F4") (pinfunction "F4_F4") (pintype "passive+no_connect"))
    )
    (net (code "177") (name "unconnected-(J2-PadF5)") (class "Default")
      (node (ref "J2") (pin "F5") (pinfunction "F5_F5") (pintype "passive+no_connect"))
    )
    (net (code "178") (name "unconnected-(J2-PadF7)") (class "Default")
      (node (ref "J2") (pin "F7") (pinfunction "F7_F7") (pintype "passive+no_connect"))
    )
    (net (code "179") (name "unconnected-(J2-PadF8)") (class "Default")
      (node (ref "J2") (pin "F8") (pinfunction "F8_F8") (pintype "passive+no_connect"))
    )
    (net (code "180") (name "unconnected-(J2-PadF16)") (class "Default")
      (node (ref "J2") (pin "F16") (pinfunction "F16_F16") (pintype "passive+no_connect"))
    )
    (net (code "181") (name "unconnected-(J2-PadF17)") (class "Default")
      (node (ref "J2") (pin "F17") (pinfunction "F17_F17") (pintype "passive+no_connect"))
    )
    (net (code "182") (name "unconnected-(J2-PadF19)") (class "Default")
      (node (ref "J2") (pin "F19") (pinfunction "F19_F19") (pintype "passive+no_connect"))
    )
    (net (code "183") (name "unconnected-(J2-PadF20)") (class "Default")
      (node (ref "J2") (pin "F20") (pinfunction "F20_F20") (pintype "passive+no_connect"))
    )
    (net (code "184") (name "unconnected-(J2-PadF28)") (class "Default")
      (node (ref "J2") (pin "F28") (pinfunction "F28_F28") (pintype "passive+no_connect"))
    )
    (net (code "185") (name "unconnected-(J2-PadF29)") (class "Default")
      (node (ref "J2") (pin "F29") (pinfunction "F29_F29") (pintype "passive+no_connect"))
    )
    (net (code "186") (name "unconnected-(J2-PadF31)") (class "Default")
      (node (ref "J2") (pin "F31") (pinfunction "F31_F31") (pintype "passive+no_connect"))
    )
    (net (code "187") (name "unconnected-(J2-PadF32)") (class "Default")
      (node (ref "J2") (pin "F32") (pinfunction "F32_F32") (pintype "passive+no_connect"))
    )
    (net (code "188") (name "unconnected-(J2-PadF34)") (class "Default")
      (node (ref "J2") (pin "F34") (pinfunction "F34_F34") (pintype "passive+no_connect"))
    )
    (net (code "189") (name "unconnected-(J2-PadF35)") (class "Default")
      (node (ref "J2") (pin "F35") (pinfunction "F35_F35") (pintype "passive+no_connect"))
    )
    (net (code "190") (name "unconnected-(J2-PadF37)") (class "Default")
      (node (ref "J2") (pin "F37") (pinfunction "F37_F37") (pintype "passive+no_connect"))
    )
    (net (code "191") (name "unconnected-(J2-PadF38)") (class "Default")
      (node (ref "J2") (pin "F38") (pinfunction "F38_F38") (pintype "passive+no_connect"))
    )
    (net (code "192") (name "unconnected-(J2-PadG2)") (class "Default")
      (node (ref "J2") (pin "G2") (pinfunction "G2_G2") (pintype "passive+no_connect"))
    )
    (net (code "193") (name "unconnected-(J2-PadG3)") (class "Default")
      (node (ref "J2") (pin "G3") (pinfunction "G3_G3") (pintype "passive+no_connect"))
    )
    (net (code "194") (name "unconnected-(J2-PadG12)") (class "Default")
      (node (ref "J2") (pin "G12") (pinfunction "G12_G12") (pintype "passive+no_connect"))
    )
    (net (code "195") (name "unconnected-(J2-PadG13)") (class "Default")
      (node (ref "J2") (pin "G13") (pinfunction "G13_G13") (pintype "passive+no_connect"))
    )
    (net (code "196") (name "unconnected-(J2-PadG15)") (class "Default")
      (node (ref "J2") (pin "G15") (pinfunction "G15_G15") (pintype "passive+no_connect"))
    )
    (net (code "197") (name "unconnected-(J2-PadG16)") (class "Default")
      (node (ref "J2") (pin "G16") (pinfunction "G16_G16") (pintype "passive+no_connect"))
    )
    (net (code "198") (name "unconnected-(J2-PadG18)") (class "Default")
      (node (ref "J2") (pin "G18") (pinfunction "G18_G18") (pintype "passive+no_connect"))
    )
    (net (code "199") (name "unconnected-(J2-PadG19)") (class "Default")
      (node (ref "J2") (pin "G19") (pinfunction "G19_G19") (pintype "passive+no_connect"))
    )
    (net (code "200") (name "unconnected-(J2-PadG21)") (class "Default")
      (node (ref "J2") (pin "G21") (pinfunction "G21_G21") (pintype "passive+no_connect"))
    )
    (net (code "201") (name "unconnected-(J2-PadG22)") (class "Default")
      (node (ref "J2") (pin "G22") (pinfunction "G22_G22") (pintype "passive+no_connect"))
    )
    (net (code "202") (name "unconnected-(J2-PadG27)") (class "Default")
      (node (ref "J2") (pin "G27") (pinfunction "G27_G27") (pintype "passive+no_connect"))
    )
    (net (code "203") (name "unconnected-(J2-PadG28)") (class "Default")
      (node (ref "J2") (pin "G28") (pinfunction "G28_G28") (pintype "passive+no_connect"))
    )
    (net (code "204") (name "unconnected-(J2-PadG30)") (class "Default")
      (node (ref "J2") (pin "G30") (pinfunction "G30_G30") (pintype "passive+no_connect"))
    )
    (net (code "205") (name "unconnected-(J2-PadG31)") (class "Default")
      (node (ref "J2") (pin "G31") (pinfunction "G31_G31") (pintype "passive+no_connect"))
    )
    (net (code "206") (name "unconnected-(J2-PadG33)") (class "Default")
      (node (ref "J2") (pin "G33") (pinfunction "G33_G33") (pintype "passive+no_connect"))
    )
    (net (code "207") (name "unconnected-(J2-PadG34)") (class "Default")
      (node (ref "J2") (pin "G34") (pinfunction "G34_G34") (pintype "passive+no_connect"))
    )
    (net (code "208") (name "unconnected-(J2-PadG36)") (class "Default")
      (node (ref "J2") (pin "G36") (pinfunction "G36_G36") (pintype "passive+no_connect"))
    )
    (net (code "209") (name "unconnected-(J2-PadG37)") (class "Default")
      (node (ref "J2") (pin "G37") (pinfunction "G37_G37") (pintype "passive+no_connect"))
    )
    (net (code "210") (name "unconnected-(J2-PadH4)") (class "Default")
      (node (ref "J2") (pin "H4") (pinfunction "H4_H4") (pintype "passive+no_connect"))
    )
    (net (code "211") (name "unconnected-(J2-PadH5)") (class "Default")
      (node (ref "J2") (pin "H5") (pinfunction "H5_H5") (pintype "passive+no_connect"))
    )
    (net (code "212") (name "unconnected-(J2-PadH7)") (class "Default")
      (node (ref "J2") (pin "H7") (pinfunction "H7_H7") (pintype "passive+no_connect"))
    )
    (net (code "213") (name "unconnected-(J2-PadH8)") (class "Default")
      (node (ref "J2") (pin "H8") (pinfunction "H8_H8") (pintype "passive+no_connect"))
    )
    (net (code "214") (name "unconnected-(J2-PadH10)") (class "Default")
      (node (ref "J2") (pin "H10") (pinfunction "H10_H10") (pintype "passive+no_connect"))
    )
    (net (code "215") (name "unconnected-(J2-PadH11)") (class "Default")
      (node (ref "J2") (pin "H11") (pinfunction "H11_H11") (pintype "passive+no_connect"))
    )
    (net (code "216") (name "unconnected-(J2-PadH13)") (class "Default")
      (node (ref "J2") (pin "H13") (pinfunction "H13_H13") (pintype "passive+no_connect"))
    )
    (net (code "217") (name "unconnected-(J2-PadH14)") (class "Default")
      (node (ref "J2") (pin "H14") (pinfunction "H14_H14") (pintype "passive+no_connect"))
    )
    (net (code "218") (name "unconnected-(J2-PadH16)") (class "Default")
      (node (ref "J2") (pin "H16") (pinfunction "H16_H16") (pintype "passive+no_connect"))
    )
    (net (code "219") (name "unconnected-(J2-PadH17)") (class "Default")
      (node (ref "J2") (pin "H17") (pinfunction "H17_H17") (pintype "passive+no_connect"))
    )
    (net (code "220") (name "unconnected-(J2-PadH19)") (class "Default")
      (node (ref "J2") (pin "H19") (pinfunction "H19_H19") (pintype "passive+no_connect"))
    )
    (net (code "221") (name "unconnected-(J2-PadH20)") (class "Default")
      (node (ref "J2") (pin "H20") (pinfunction "H20_H20") (pintype "passive+no_connect"))
    )
    (net (code "222") (name "unconnected-(J2-PadH22)") (class "Default")
      (node (ref "J2") (pin "H22") (pinfunction "H22_H22") (pintype "passive+no_connect"))
    )
    (net (code "223") (name "unconnected-(J2-PadH23)") (class "Default")
      (node (ref "J2") (pin "H23") (pinfunction "H23_H23") (pintype "passive+no_connect"))
    )
    (net (code "224") (name "unconnected-(J2-PadH25)") (class "Default")
      (node (ref "J2") (pin "H25") (pinfunction "H25_H25") (pintype "passive+no_connect"))
    )
    (net (code "225") (name "unconnected-(J2-PadH26)") (class "Default")
      (node (ref "J2") (pin "H26") (pinfunction "H26_H26") (pintype "passive+no_connect"))
    )
    (net (code "226") (name "unconnected-(J2-PadH28)") (class "Default")
      (node (ref "J2") (pin "H28") (pinfunction "H28_H28") (pintype "passive+no_connect"))
    )
    (net (code "227") (name "unconnected-(J2-PadH29)") (class "Default")
      (node (ref "J2") (pin "H29") (pinfunction "H29_H29") (pintype "passive+no_connect"))
    )
    (net (code "228") (name "unconnected-(J2-PadH31)") (class "Default")
      (node (ref "J2") (pin "H31") (pinfunction "H31_H31") (pintype "passive+no_connect"))
    )
    (net (code "229") (name "unconnected-(J2-PadH32)") (class "Default")
      (node (ref "J2") (pin "H32") (pinfunction "H32_H32") (pintype "passive+no_connect"))
    )
    (net (code "230") (name "unconnected-(J2-PadH34)") (class "Default")
      (node (ref "J2") (pin "H34") (pinfunction "H34_H34") (pintype "passive+no_connect"))
    )
    (net (code "231") (name "unconnected-(J2-PadH35)") (class "Default")
      (node (ref "J2") (pin "H35") (pinfunction "H35_H35") (pintype "passive+no_connect"))
    )
    (net (code "232") (name "unconnected-(J2-PadH37)") (class "Default")
      (node (ref "J2") (pin "H37") (pinfunction "H37_H37") (pintype "passive+no_connect"))
    )
    (net (code "233") (name "unconnected-(J2-PadH38)") (class "Default")
      (node (ref "J2") (pin "H38") (pinfunction "H38_H38") (pintype "passive+no_connect"))
    )
    (net (code "234") (name "unconnected-(J2-PadJ21)") (class "Default")
      (node (ref "J2") (pin "J21") (pinfunction "J21_J21") (pintype "passive+no_connect"))
    )
    (net (code "235") (name "unconnected-(J2-PadJ22)") (class "Default")
      (node (ref "J2") (pin "J22") (pinfunction "J22_J22") (pintype "passive+no_connect"))
    )
    (net (code "236") (name "unconnected-(J2-PadJ36)") (class "Default")
      (node (ref "J2") (pin "J36") (pinfunction "J36_J36") (pintype "passive+no_connect"))
    )
    (net (code "237") (name "unconnected-(J2-PadJ37)") (class "Default")
      (node (ref "J2") (pin "J37") (pinfunction "J37_J37") (pintype "passive+no_connect"))
    )
    (net (code "238") (name "unconnected-(J2-PadK4)") (class "Default")
      (node (ref "J2") (pin "K4") (pinfunction "K4_K4") (pintype "passive+no_connect"))
    )
    (net (code "239") (name "unconnected-(J2-PadK5)") (class "Default")
      (node (ref "J2") (pin "K5") (pinfunction "K5_K5") (pintype "passive+no_connect"))
    )
    (net (code "240") (name "unconnected-(J2-PadK19)") (class "Default")
      (node (ref "J2") (pin "K19") (pinfunction "K19_K19") (pintype "passive+no_connect"))
    )
    (net (code "241") (name "unconnected-(J2-PadK20)") (class "Default")
      (node (ref "J2") (pin "K20") (pinfunction "K20_K20") (pintype "passive+no_connect"))
    )
    (net (code "242") (name "unconnected-(J2-PadK22)") (class "Default")
      (node (ref "J2") (pin "K22") (pinfunction "K22_K22") (pintype "passive+no_connect"))
    )
    (net (code "243") (name "unconnected-(J2-PadK23)") (class "Default")
      (node (ref "J2") (pin "K23") (pinfunction "K23_K23") (pintype "passive+no_connect"))
    )
    (net (code "244") (name "unconnected-(J2-PadK38)") (class "Default")
      (node (ref "J2") (pin "K38") (pinfunction "K38_K38") (pintype "passive+no_connect"))
    )
  )
)
